# SCH2_Switching.net
KiCad netlist of a schematic drawn in Altium Designer
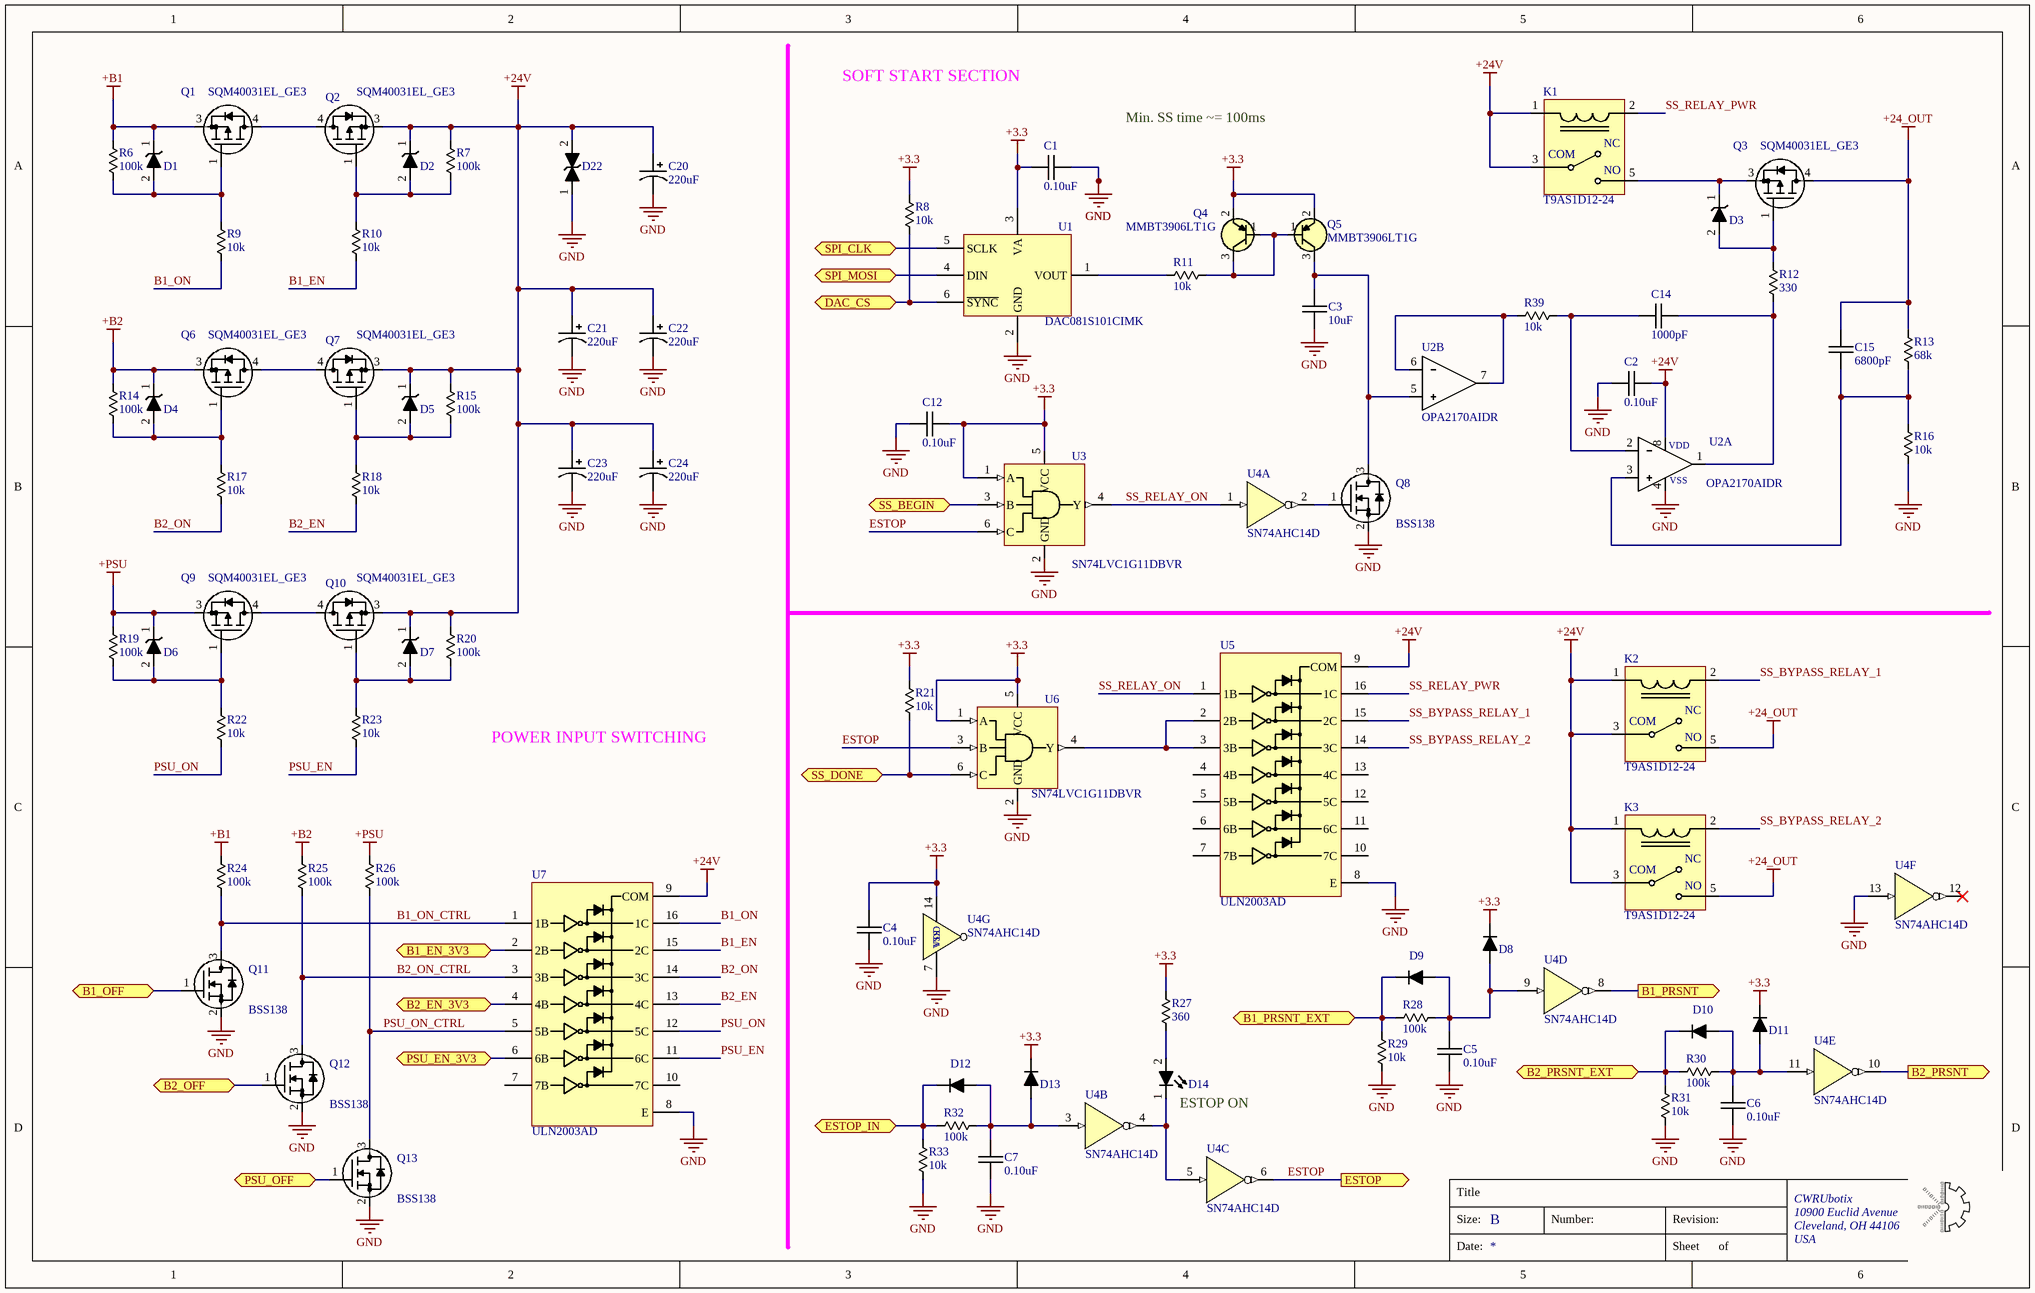
[diagram p0: SCH2_Switching.SchDoc]

(export (version "E")
  (design (tool "Eeschema 10.0.6"))
  (components
    (comp (ref "C1")
      (value "0.10uF")
      (footprint "chip_0805")
      (description "CAP, 0.10uF, 10%, 25V, X7R, 0805")
      (fields (field (name "PART NUMBER") "CAP-00071") (field (name "TOLERANCE") "10%"))
      (libsource (lib "Capacitors$") (part "CAP-00071"))
    )
    (comp (ref "C2")
      (value "0.10uF")
      (footprint "chip_0805")
      (description "CAP, 0.10uF, 10%, 25V, X7R, 0805")
      (fields (field (name "PART NUMBER") "CAP-00071") (field (name "TOLERANCE") "10%"))
      (libsource (lib "Capacitors$") (part "CAP-00071"))
    )
    (comp (ref "C3")
      (value "10uF")
      (footprint "chip_1206")
      (description "CAP, 10uF, ±10%, 25V, X7R, 1206")
      (fields (field (name "PART NUMBER") "CAP-00539") (field (name "TOLERANCE") "±10%"))
      (libsource (lib "Capacitors$") (part "CAP-00539"))
    )
    (comp (ref "C4")
      (value "0.10uF")
      (footprint "chip_0805")
      (description "CAP, 0.10uF, 10%, 25V, X7R, 0805")
      (fields (field (name "PART NUMBER") "CAP-00071") (field (name "TOLERANCE") "10%"))
      (libsource (lib "Capacitors$") (part "CAP-00071"))
    )
    (comp (ref "C5")
      (value "0.10uF")
      (footprint "chip_0805")
      (description "CAP, 0.10uF, 10%, 25V, X7R, 0805")
      (fields (field (name "PART NUMBER") "CAP-00071") (field (name "TOLERANCE") "10%"))
      (libsource (lib "Capacitors$") (part "CAP-00071"))
    )
    (comp (ref "C6")
      (value "0.10uF")
      (footprint "chip_0805")
      (description "CAP, 0.10uF, 10%, 25V, X7R, 0805")
      (fields (field (name "PART NUMBER") "CAP-00071") (field (name "TOLERANCE") "10%"))
      (libsource (lib "Capacitors$") (part "CAP-00071"))
    )
    (comp (ref "C7")
      (value "0.10uF")
      (footprint "chip_0805")
      (description "CAP, 0.10uF, 10%, 25V, X7R, 0805")
      (fields (field (name "PART NUMBER") "CAP-00071") (field (name "TOLERANCE") "10%"))
      (libsource (lib "Capacitors$") (part "CAP-00071"))
    )
    (comp (ref "C12")
      (value "0.10uF")
      (footprint "chip_0805")
      (description "CAP, 0.10uF, 10%, 16V, X7R, 0805")
      (fields (field (name "PART NUMBER") "CAP-00069") (field (name "TOLERANCE") "10%"))
      (libsource (lib "Capacitors$") (part "CAP-00069"))
    )
    (comp (ref "C14")
      (value "1000pF")
      (footprint "chip_0805")
      (description "CAP, 1000pF, 10%, 50V, X7R, 0805")
      (fields (field (name "PART NUMBER") "CAP-00009") (field (name "TOLERANCE") "10%"))
      (libsource (lib "Capacitors$") (part "CAP-00009"))
    )
    (comp (ref "C15")
      (value "6800pF")
      (footprint "chip_0805")
      (description "CAP, 6800pF, 10%, 50V, X7R, 0805")
      (fields (field (name "PART NUMBER") "CAP-00035") (field (name "TOLERANCE") "10%"))
      (libsource (lib "Capacitors$") (part "CAP-00035"))
    )
    (comp (ref "C20")
      (value "220uF")
      (footprint "CP_RADIAL_D10.0_P5.0_H20.0")
      (description "CAP, 220uF, ±20%, 63V, Al, 5000hrs @ 105°C")
      (fields (field (name "PART NUMBER") "CAP-00591") (field (name "TOLERANCE") "±20%"))
      (libsource (lib "Capacitors$") (part "CAP-00591"))
    )
    (comp (ref "C21")
      (value "220uF")
      (footprint "CP_RADIAL_D10.0_P5.0_H20.0")
      (description "CAP, 220uF, ±20%, 63V, Al, 5000hrs @ 105°C")
      (fields (field (name "PART NUMBER") "CAP-00591") (field (name "TOLERANCE") "±20%"))
      (libsource (lib "Capacitors$") (part "CAP-00591"))
    )
    (comp (ref "C22")
      (value "220uF")
      (footprint "CP_RADIAL_D10.0_P5.0_H20.0")
      (description "CAP, 220uF, ±20%, 63V, Al, 5000hrs @ 105°C")
      (fields (field (name "PART NUMBER") "CAP-00591") (field (name "TOLERANCE") "±20%"))
      (libsource (lib "Capacitors$") (part "CAP-00591"))
    )
    (comp (ref "C23")
      (value "220uF")
      (footprint "CP_RADIAL_D10.0_P5.0_H20.0")
      (description "CAP, 220uF, ±20%, 63V, Al, 5000hrs @ 105°C")
      (fields (field (name "PART NUMBER") "CAP-00591") (field (name "TOLERANCE") "±20%"))
      (libsource (lib "Capacitors$") (part "CAP-00591"))
    )
    (comp (ref "C24")
      (value "220uF")
      (footprint "CP_RADIAL_D10.0_P5.0_H20.0")
      (description "CAP, 220uF, ±20%, 63V, Al, 5000hrs @ 105°C")
      (fields (field (name "PART NUMBER") "CAP-00591") (field (name "TOLERANCE") "±20%"))
      (libsource (lib "Capacitors$") (part "CAP-00591"))
    )
    (comp (ref "D1")
      (value "diode_1")
      (footprint "sod123_0")
      (description "Dio, Zener, 12V 5% 500mW SOD-123")
      (fields (field (name "PART NUMBER") "DIO-00072") (field (name "TOLERANCE") "5%"))
      (libsource (lib "Diodes$") (part "DIO-00072"))
    )
    (comp (ref "D2")
      (value "diode_1")
      (footprint "sod123_0")
      (description "Dio, Zener, 12V 5% 500mW SOD-123")
      (fields (field (name "PART NUMBER") "DIO-00072") (field (name "TOLERANCE") "5%"))
      (libsource (lib "Diodes$") (part "DIO-00072"))
    )
    (comp (ref "D3")
      (value "diode_1")
      (footprint "sod123_0")
      (description "Dio, Zener, 12V 5% 500mW SOD-123")
      (fields (field (name "PART NUMBER") "DIO-00072") (field (name "TOLERANCE") "5%"))
      (libsource (lib "Diodes$") (part "DIO-00072"))
    )
    (comp (ref "D4")
      (value "diode_1")
      (footprint "sod123_0")
      (description "Dio, Zener, 12V 5% 500mW SOD-123")
      (fields (field (name "PART NUMBER") "DIO-00072") (field (name "TOLERANCE") "5%"))
      (libsource (lib "Diodes$") (part "DIO-00072"))
    )
    (comp (ref "D5")
      (value "diode_1")
      (footprint "sod123_0")
      (description "Dio, Zener, 12V 5% 500mW SOD-123")
      (fields (field (name "PART NUMBER") "DIO-00072") (field (name "TOLERANCE") "5%"))
      (libsource (lib "Diodes$") (part "DIO-00072"))
    )
    (comp (ref "D6")
      (value "diode_1")
      (footprint "sod123_0")
      (description "Dio, Zener, 12V 5% 500mW SOD-123")
      (fields (field (name "PART NUMBER") "DIO-00072") (field (name "TOLERANCE") "5%"))
      (libsource (lib "Diodes$") (part "DIO-00072"))
    )
    (comp (ref "D7")
      (value "diode_1")
      (footprint "sod123_0")
      (description "Dio, Zener, 12V 5% 500mW SOD-123")
      (fields (field (name "PART NUMBER") "DIO-00072") (field (name "TOLERANCE") "5%"))
      (libsource (lib "Diodes$") (part "DIO-00072"))
    )
    (comp (ref "D8")
      (value "diode_0")
      (footprint "sod123_0")
      (description "Dio, Silicon, 200mA, 1V, 100V, SOD-123")
      (fields (field (name "PART NUMBER") "DIO-00060") (field (name "MANUFACTURER") "ON Semi"))
      (libsource (lib "Diodes$") (part "DIO-00060"))
    )
    (comp (ref "D9")
      (value "diode_0")
      (footprint "sod123_0")
      (description "Dio, Silicon, 200mA, 1V, 100V, SOD-123")
      (fields (field (name "PART NUMBER") "DIO-00060") (field (name "MANUFACTURER") "ON Semi"))
      (libsource (lib "Diodes$") (part "DIO-00060"))
    )
    (comp (ref "D10")
      (value "diode_0")
      (footprint "sod123_0")
      (description "Dio, Silicon, 200mA, 1V, 100V, SOD-123")
      (fields (field (name "PART NUMBER") "DIO-00060") (field (name "MANUFACTURER") "ON Semi"))
      (libsource (lib "Diodes$") (part "DIO-00060"))
    )
    (comp (ref "D11")
      (value "diode_0")
      (footprint "sod123_0")
      (description "Dio, Silicon, 200mA, 1V, 100V, SOD-123")
      (fields (field (name "PART NUMBER") "DIO-00060") (field (name "MANUFACTURER") "ON Semi"))
      (libsource (lib "Diodes$") (part "DIO-00060"))
    )
    (comp (ref "D12")
      (value "diode_0")
      (footprint "sod123_0")
      (description "Dio, Silicon, 200mA, 1V, 100V, SOD-123")
      (fields (field (name "PART NUMBER") "DIO-00060") (field (name "MANUFACTURER") "ON Semi"))
      (libsource (lib "Diodes$") (part "DIO-00060"))
    )
    (comp (ref "D13")
      (value "diode_0")
      (footprint "sod123_0")
      (description "Dio, Silicon, 200mA, 1V, 100V, SOD-123")
      (fields (field (name "PART NUMBER") "DIO-00060") (field (name "MANUFACTURER") "ON Semi"))
      (libsource (lib "Diodes$") (part "DIO-00060"))
    )
    (comp (ref "D14")
      (value "diode_4")
      (footprint "chip_0603_LED")
      (description "LED, Blue, 0603, Low current, HELI2 Series")
      (fields (field (name "PART NUMBER") "DIO-00049") (field (name "MANUFACTURER") "Kingbright"))
      (libsource (lib "Diodes$") (part "DIO-00049"))
    )
    (comp (ref "D22")
      (value "diode_5")
      (footprint "do-214ab")
      (description "TVS, 28V, 45.5V@66A, 3kW 66A Peak, Bidirectional, DO-214AC")
      (fields (field (name "PART NUMBER") "DIO-00090") (field (name "MANUFACTURER") "ST"))
      (libsource (lib "Diodes$") (part "DIO-00090"))
    )
    (comp (ref "K1")
      (value "T9AS1D12-24")
      (footprint "TE_CONN_T9AS")
      (description "Relay, 24V Coil, 30A, SPST, 1 Form A")
      (fields (field (name "PART NUMBER") "MISC-00050") (field (name "MANUFACTURER") "TE Connectivity"))
      (libsource (lib "Misc$") (part "MISC-00050"))
    )
    (comp (ref "K2")
      (value "T9AS1D12-24")
      (footprint "TE_CONN_T9AS")
      (description "Relay, 24V Coil, 30A, SPST, 1 Form A")
      (fields (field (name "PART NUMBER") "MISC-00050") (field (name "MANUFACTURER") "TE Connectivity"))
      (libsource (lib "Misc$") (part "MISC-00050"))
    )
    (comp (ref "K3")
      (value "T9AS1D12-24")
      (footprint "TE_CONN_T9AS")
      (description "Relay, 24V Coil, 30A, SPST, 1 Form A")
      (fields (field (name "PART NUMBER") "MISC-00050") (field (name "MANUFACTURER") "TE Connectivity"))
      (libsource (lib "Misc$") (part "MISC-00050"))
    )
    (comp (ref "Q1")
      (value "SQM40031EL_GE3")
      (footprint "D2PAK-3_1")
      (description "XSTR, MOSFET P-Channel, 40V 120A 3mOhm Rds On, D2PAK")
      (fields (field (name "PART NUMBER") "XSTR-00046") (field (name "MANUFACTURER") "Vishay Siliconix"))
      (libsource (lib "Transistors$") (part "XSTR-00046"))
    )
    (comp (ref "Q2")
      (value "SQM40031EL_GE3")
      (footprint "D2PAK-3_1")
      (description "XSTR, MOSFET P-Channel, 40V 120A 3mOhm Rds On, D2PAK")
      (fields (field (name "PART NUMBER") "XSTR-00046") (field (name "MANUFACTURER") "Vishay Siliconix"))
      (libsource (lib "Transistors$") (part "XSTR-00046"))
    )
    (comp (ref "Q3")
      (value "SQM40031EL_GE3")
      (footprint "D2PAK-3_1")
      (description "XSTR, MOSFET P-Channel, 40V 120A 3mOhm Rds On, D2PAK")
      (fields (field (name "PART NUMBER") "XSTR-00046") (field (name "MANUFACTURER") "Vishay Siliconix"))
      (libsource (lib "Transistors$") (part "XSTR-00046"))
    )
    (comp (ref "Q4")
      (value "MMBT3906LT1G")
      (footprint "SOT-23-3_1")
      (description "XSTR, PNP, 200mA, 40V, Vce 0.4V, SOT-23-3")
      (fields (field (name "PART NUMBER") "XSTR-00038") (field (name "MANUFACTURER") "ON Semi"))
      (libsource (lib "Transistors$") (part "XSTR-00038"))
    )
    (comp (ref "Q5")
      (value "MMBT3906LT1G")
      (footprint "SOT-23-3_1")
      (description "XSTR, PNP, 200mA, 40V, Vce 0.4V, SOT-23-3")
      (fields (field (name "PART NUMBER") "XSTR-00038") (field (name "MANUFACTURER") "ON Semi"))
      (libsource (lib "Transistors$") (part "XSTR-00038"))
    )
    (comp (ref "Q6")
      (value "SQM40031EL_GE3")
      (footprint "D2PAK-3_1")
      (description "XSTR, MOSFET P-Channel, 40V 120A 3mOhm Rds On, D2PAK")
      (fields (field (name "PART NUMBER") "XSTR-00046") (field (name "MANUFACTURER") "Vishay Siliconix"))
      (libsource (lib "Transistors$") (part "XSTR-00046"))
    )
    (comp (ref "Q7")
      (value "SQM40031EL_GE3")
      (footprint "D2PAK-3_1")
      (description "XSTR, MOSFET P-Channel, 40V 120A 3mOhm Rds On, D2PAK")
      (fields (field (name "PART NUMBER") "XSTR-00046") (field (name "MANUFACTURER") "Vishay Siliconix"))
      (libsource (lib "Transistors$") (part "XSTR-00046"))
    )
    (comp (ref "Q8")
      (value "BSS138")
      (footprint "sot-23-3")
      (description "XSTR NMOS, 220mA, 50V, Vgs 1.3V, SOT-23-3")
      (fields (field (name "PART NUMBER") "XSTR-00017") (field (name "MANUFACTURER") "ON Semi"))
      (libsource (lib "Transistors$") (part "XSTR-00017"))
    )
    (comp (ref "Q9")
      (value "SQM40031EL_GE3")
      (footprint "D2PAK-3_1")
      (description "XSTR, MOSFET P-Channel, 40V 120A 3mOhm Rds On, D2PAK")
      (fields (field (name "PART NUMBER") "XSTR-00046") (field (name "MANUFACTURER") "Vishay Siliconix"))
      (libsource (lib "Transistors$") (part "XSTR-00046"))
    )
    (comp (ref "Q10")
      (value "SQM40031EL_GE3")
      (footprint "D2PAK-3_1")
      (description "XSTR, MOSFET P-Channel, 40V 120A 3mOhm Rds On, D2PAK")
      (fields (field (name "PART NUMBER") "XSTR-00046") (field (name "MANUFACTURER") "Vishay Siliconix"))
      (libsource (lib "Transistors$") (part "XSTR-00046"))
    )
    (comp (ref "Q11")
      (value "BSS138")
      (footprint "sot-23-3")
      (description "XSTR NMOS, 220mA, 50V, Vgs 1.3V, SOT-23-3")
      (fields (field (name "PART NUMBER") "XSTR-00017") (field (name "MANUFACTURER") "ON Semi"))
      (libsource (lib "Transistors$") (part "XSTR-00017"))
    )
    (comp (ref "Q12")
      (value "BSS138")
      (footprint "sot-23-3")
      (description "XSTR NMOS, 220mA, 50V, Vgs 1.3V, SOT-23-3")
      (fields (field (name "PART NUMBER") "XSTR-00017") (field (name "MANUFACTURER") "ON Semi"))
      (libsource (lib "Transistors$") (part "XSTR-00017"))
    )
    (comp (ref "Q13")
      (value "BSS138")
      (footprint "sot-23-3")
      (description "XSTR NMOS, 220mA, 50V, Vgs 1.3V, SOT-23-3")
      (fields (field (name "PART NUMBER") "XSTR-00017") (field (name "MANUFACTURER") "ON Semi"))
      (libsource (lib "Transistors$") (part "XSTR-00017"))
    )
    (comp (ref "R6")
      (value "100k")
      (footprint "chip_0805")
      (description "RES SMD 100K OHM 1% 1/8W 0805")
      (fields (field (name "PART NUMBER") "RES-00302") (field (name "TOLERANCE") "1%"))
      (libsource (lib "Resistors$") (part "RES-00302"))
    )
    (comp (ref "R7")
      (value "100k")
      (footprint "chip_0805")
      (description "RES SMD 100K OHM 1% 1/8W 0805")
      (fields (field (name "PART NUMBER") "RES-00302") (field (name "TOLERANCE") "1%"))
      (libsource (lib "Resistors$") (part "RES-00302"))
    )
    (comp (ref "R8")
      (value "10k")
      (footprint "chip_0805")
      (description "RES SMD 10K OHM 1% 1/8W 0805")
      (fields (field (name "PART NUMBER") "RES-00307") (field (name "TOLERANCE") "1%"))
      (libsource (lib "Resistors$") (part "RES-00307"))
    )
    (comp (ref "R9")
      (value "10k")
      (footprint "chip_0805")
      (description "RES SMD 10K OHM 1% 1/8W 0805")
      (fields (field (name "PART NUMBER") "RES-00307") (field (name "TOLERANCE") "1%"))
      (libsource (lib "Resistors$") (part "RES-00307"))
    )
    (comp (ref "R10")
      (value "10k")
      (footprint "chip_0805")
      (description "RES SMD 10K OHM 1% 1/8W 0805")
      (fields (field (name "PART NUMBER") "RES-00307") (field (name "TOLERANCE") "1%"))
      (libsource (lib "Resistors$") (part "RES-00307"))
    )
    (comp (ref "R11")
      (value "10k")
      (footprint "chip_0805")
      (description "RES SMD 10K OHM 1% 1/8W 0805")
      (fields (field (name "PART NUMBER") "RES-00307") (field (name "TOLERANCE") "1%"))
      (libsource (lib "Resistors$") (part "RES-00307"))
    )
    (comp (ref "R12")
      (value "330")
      (footprint "chip_0805")
      (description "RES SMD 330 OHM 1% 1/8W 0805")
      (fields (field (name "PART NUMBER") "RES-00222") (field (name "TOLERANCE") "1%"))
      (libsource (lib "Resistors$") (part "RES-00222"))
    )
    (comp (ref "R13")
      (value "68k")
      (footprint "chip_0805")
      (description "RES SMD 68K OHM 1% 1/8W 0805 100ppm")
      (fields (field (name "PART NUMBER") "RES-00724") (field (name "TOLERANCE") "1%"))
      (libsource (lib "Resistors$") (part "RES-00724"))
    )
    (comp (ref "R14")
      (value "100k")
      (footprint "chip_0805")
      (description "RES SMD 100K OHM 1% 1/8W 0805")
      (fields (field (name "PART NUMBER") "RES-00302") (field (name "TOLERANCE") "1%"))
      (libsource (lib "Resistors$") (part "RES-00302"))
    )
    (comp (ref "R15")
      (value "100k")
      (footprint "chip_0805")
      (description "RES SMD 100K OHM 1% 1/8W 0805")
      (fields (field (name "PART NUMBER") "RES-00302") (field (name "TOLERANCE") "1%"))
      (libsource (lib "Resistors$") (part "RES-00302"))
    )
    (comp (ref "R16")
      (value "10k")
      (footprint "chip_0805")
      (description "RES SMD 10K OHM 1% 1/8W 0805")
      (fields (field (name "PART NUMBER") "RES-00307") (field (name "TOLERANCE") "1%"))
      (libsource (lib "Resistors$") (part "RES-00307"))
    )
    (comp (ref "R17")
      (value "10k")
      (footprint "chip_0805")
      (description "RES SMD 10K OHM 1% 1/8W 0805")
      (fields (field (name "PART NUMBER") "RES-00307") (field (name "TOLERANCE") "1%"))
      (libsource (lib "Resistors$") (part "RES-00307"))
    )
    (comp (ref "R18")
      (value "10k")
      (footprint "chip_0805")
      (description "RES SMD 10K OHM 1% 1/8W 0805")
      (fields (field (name "PART NUMBER") "RES-00307") (field (name "TOLERANCE") "1%"))
      (libsource (lib "Resistors$") (part "RES-00307"))
    )
    (comp (ref "R19")
      (value "100k")
      (footprint "chip_0805")
      (description "RES SMD 100K OHM 1% 1/8W 0805")
      (fields (field (name "PART NUMBER") "RES-00302") (field (name "TOLERANCE") "1%"))
      (libsource (lib "Resistors$") (part "RES-00302"))
    )
    (comp (ref "R20")
      (value "100k")
      (footprint "chip_0805")
      (description "RES SMD 100K OHM 1% 1/8W 0805")
      (fields (field (name "PART NUMBER") "RES-00302") (field (name "TOLERANCE") "1%"))
      (libsource (lib "Resistors$") (part "RES-00302"))
    )
    (comp (ref "R21")
      (value "10k")
      (footprint "chip_0805")
      (description "RES SMD 10K OHM 1% 1/8W 0805")
      (fields (field (name "PART NUMBER") "RES-00307") (field (name "TOLERANCE") "1%"))
      (libsource (lib "Resistors$") (part "RES-00307"))
    )
    (comp (ref "R22")
      (value "10k")
      (footprint "chip_0805")
      (description "RES SMD 10K OHM 1% 1/8W 0805")
      (fields (field (name "PART NUMBER") "RES-00307") (field (name "TOLERANCE") "1%"))
      (libsource (lib "Resistors$") (part "RES-00307"))
    )
    (comp (ref "R23")
      (value "10k")
      (footprint "chip_0805")
      (description "RES SMD 10K OHM 1% 1/8W 0805")
      (fields (field (name "PART NUMBER") "RES-00307") (field (name "TOLERANCE") "1%"))
      (libsource (lib "Resistors$") (part "RES-00307"))
    )
    (comp (ref "R24")
      (value "100k")
      (footprint "chip_0805")
      (description "RES SMD 100K OHM 1% 1/8W 0805")
      (fields (field (name "PART NUMBER") "RES-00302") (field (name "TOLERANCE") "1%"))
      (libsource (lib "Resistors$") (part "RES-00302"))
    )
    (comp (ref "R25")
      (value "100k")
      (footprint "chip_0805")
      (description "RES SMD 100K OHM 1% 1/8W 0805")
      (fields (field (name "PART NUMBER") "RES-00302") (field (name "TOLERANCE") "1%"))
      (libsource (lib "Resistors$") (part "RES-00302"))
    )
    (comp (ref "R26")
      (value "100k")
      (footprint "chip_0805")
      (description "RES SMD 100K OHM 1% 1/8W 0805")
      (fields (field (name "PART NUMBER") "RES-00302") (field (name "TOLERANCE") "1%"))
      (libsource (lib "Resistors$") (part "RES-00302"))
    )
    (comp (ref "R27")
      (value "360")
      (footprint "chip_0805")
      (description "RES SMD 360 OHM 1% 1/8W 0805")
      (fields (field (name "PART NUMBER") "RES-00226") (field (name "TOLERANCE") "1%"))
      (libsource (lib "Resistors$") (part "RES-00226"))
    )
    (comp (ref "R28")
      (value "100k")
      (footprint "chip_0805")
      (description "RES SMD 100K OHM 1% 1/8W 0805")
      (fields (field (name "PART NUMBER") "RES-00302") (field (name "TOLERANCE") "1%"))
      (libsource (lib "Resistors$") (part "RES-00302"))
    )
    (comp (ref "R29")
      (value "10k")
      (footprint "chip_0805")
      (description "RES SMD 10K OHM 1% 1/8W 0805")
      (fields (field (name "PART NUMBER") "RES-00307") (field (name "TOLERANCE") "1%"))
      (libsource (lib "Resistors$") (part "RES-00307"))
    )
    (comp (ref "R30")
      (value "100k")
      (footprint "chip_0805")
      (description "RES SMD 100K OHM 1% 1/8W 0805")
      (fields (field (name "PART NUMBER") "RES-00302") (field (name "TOLERANCE") "1%"))
      (libsource (lib "Resistors$") (part "RES-00302"))
    )
    (comp (ref "R31")
      (value "10k")
      (footprint "chip_0805")
      (description "RES SMD 10K OHM 1% 1/8W 0805")
      (fields (field (name "PART NUMBER") "RES-00307") (field (name "TOLERANCE") "1%"))
      (libsource (lib "Resistors$") (part "RES-00307"))
    )
    (comp (ref "R32")
      (value "100k")
      (footprint "chip_0805")
      (description "RES SMD 100K OHM 1% 1/8W 0805")
      (fields (field (name "PART NUMBER") "RES-00302") (field (name "TOLERANCE") "1%"))
      (libsource (lib "Resistors$") (part "RES-00302"))
    )
    (comp (ref "R33")
      (value "10k")
      (footprint "chip_0805")
      (description "RES SMD 10K OHM 1% 1/8W 0805")
      (fields (field (name "PART NUMBER") "RES-00307") (field (name "TOLERANCE") "1%"))
      (libsource (lib "Resistors$") (part "RES-00307"))
    )
    (comp (ref "R39")
      (value "10k")
      (footprint "chip_0805")
      (description "RES SMD 10K OHM 1% 1/8W 0805")
      (fields (field (name "PART NUMBER") "RES-00307") (field (name "TOLERANCE") "1%"))
      (libsource (lib "Resistors$") (part "RES-00307"))
    )
    (comp (ref "U1")
      (value "DAC081S101CIMK")
      (footprint "TSOT-23-6")
      (description "IC, DAC, 8-bit, Rail-Rail Output, SPI, 2.7~5.5V")
      (fields (field (name "PART NUMBER") "ANLG-00080") (field (name "MANUFACTURER") "TI"))
      (libsource (lib "Analog$") (part "ANLG-00080"))
    )
    (comp (ref "U2")
      (value "OPA2170AIDR")
      (footprint "SO-8_1")
      (description "Op Amp, Dual, Rail-Rail, 2.7~36V, 2.1-MHz, SOIC-8")
      (fields (field (name "PART NUMBER") "ANLG-00068") (field (name "MANUFACTURER") "TI"))
      (libsource (lib "Analog$") (part "ANLG-00068"))
    )
    (comp (ref "U3")
      (value "SN74LVC1G11DBVR")
      (footprint "sot-23-6")
      (description "IC, AND Gate, Single 3-Input, 1.65-5.5V, SOT-23-6")
      (fields (field (name "PART NUMBER") "LOGIC-00042") (field (name "MANUFACTURER") "TI"))
      (libsource (lib "Logic$") (part "LOGIC-00042"))
    )
    (comp (ref "U4")
      (value "SN74AHC14D")
      (footprint "SO-14")
      (description "IC, Inverter, Hex, Schmitt Triggered Inputs, SOIC-14, SN74ACH14D")
      (fields (field (name "PART NUMBER") "LOGIC-00014") (field (name "MANUFACTURER") "TI"))
      (libsource (lib "Logic$") (part "LOGIC-00014"))
    )
    (comp (ref "U5")
      (value "ULN2003AD")
      (footprint "SO-16_1")
      (description "IC, 7 NPN Darlington Array, 50V 500mA")
      (fields (field (name "PART NUMBER") "ANLG-00079") (field (name "MANUFACTURER") "TI"))
      (libsource (lib "Analog$") (part "ANLG-00079"))
    )
    (comp (ref "U6")
      (value "SN74LVC1G11DBVR")
      (footprint "sot-23-6")
      (description "IC, AND Gate, Single 3-Input, 1.65-5.5V, SOT-23-6")
      (fields (field (name "PART NUMBER") "LOGIC-00042") (field (name "MANUFACTURER") "TI"))
      (libsource (lib "Logic$") (part "LOGIC-00042"))
    )
    (comp (ref "U7")
      (value "ULN2003AD")
      (footprint "SO-16_1")
      (description "IC, 7 NPN Darlington Array, 50V 500mA")
      (fields (field (name "PART NUMBER") "ANLG-00079") (field (name "MANUFACTURER") "TI"))
      (libsource (lib "Analog$") (part "ANLG-00079"))
    )
  )
  (nets
    (net (code "1") (name "+3.3") (class "Default")
      (node (ref "C1") (pin "2") (pinfunction "2_2") (pintype "passive"))
      (node (ref "C12") (pin "2") (pinfunction "2_2") (pintype "passive"))
      (node (ref "C4") (pin "2") (pinfunction "2_2") (pintype "passive"))
      (node (ref "D11") (pin "1") (pinfunction "1_1") (pintype "passive"))
      (node (ref "D13") (pin "1") (pinfunction "1_1") (pintype "passive"))
      (node (ref "D8") (pin "1") (pinfunction "1_1") (pintype "passive"))
      (node (ref "Q4") (pin "2") (pinfunction "E_2") (pintype "passive"))
      (node (ref "Q5") (pin "2") (pinfunction "E_2") (pintype "passive"))
      (node (ref "R21") (pin "2") (pinfunction "2_2") (pintype "passive"))
      (node (ref "R27") (pin "1") (pinfunction "1_1") (pintype "passive"))
      (node (ref "R8") (pin "2") (pinfunction "2_2") (pintype "passive"))
      (node (ref "U1") (pin "3") (pinfunction "VA_3") (pintype "passive"))
      (node (ref "U3") (pin "1") (pinfunction "A_1") (pintype "input"))
      (node (ref "U3") (pin "5") (pinfunction "VCC_5") (pintype "power_in"))
      (node (ref "U4") (pin "14") (pinfunction "VDD_14") (pintype "power_in"))
      (node (ref "U6") (pin "1") (pinfunction "A_1") (pintype "input"))
      (node (ref "U6") (pin "5") (pinfunction "VCC_5") (pintype "power_in"))
    )
    (net (code "2") (name "+24V") (class "Default")
      (node (ref "C2") (pin "2") (pinfunction "2_2") (pintype "passive"))
      (node (ref "C20") (pin "1") (pinfunction "1_1") (pintype "passive"))
      (node (ref "C21") (pin "1") (pinfunction "1_1") (pintype "passive"))
      (node (ref "C22") (pin "1") (pinfunction "1_1") (pintype "passive"))
      (node (ref "C23") (pin "1") (pinfunction "1_1") (pintype "passive"))
      (node (ref "C24") (pin "1") (pinfunction "1_1") (pintype "passive"))
      (node (ref "D2") (pin "1") (pinfunction "1_1") (pintype "passive"))
      (node (ref "D22") (pin "2") (pinfunction "2_2") (pintype "passive"))
      (node (ref "D5") (pin "1") (pinfunction "1_1") (pintype "passive"))
      (node (ref "D7") (pin "1") (pinfunction "1_1") (pintype "passive"))
      (node (ref "K1") (pin "1") (pinfunction "1_1") (pintype "passive"))
      (node (ref "K1") (pin "3") (pinfunction "COM_3") (pintype "passive"))
      (node (ref "K2") (pin "1") (pinfunction "1_1") (pintype "passive"))
      (node (ref "K2") (pin "3") (pinfunction "COM_3") (pintype "passive"))
      (node (ref "K3") (pin "1") (pinfunction "1_1") (pintype "passive"))
      (node (ref "K3") (pin "3") (pinfunction "COM_3") (pintype "passive"))
      (node (ref "Q10") (pin "3") (pinfunction "S_3") (pintype "passive"))
      (node (ref "Q2") (pin "3") (pinfunction "S_3") (pintype "passive"))
      (node (ref "Q7") (pin "3") (pinfunction "S_3") (pintype "passive"))
      (node (ref "R15") (pin "1") (pinfunction "1_1") (pintype "passive"))
      (node (ref "R20") (pin "1") (pinfunction "1_1") (pintype "passive"))
      (node (ref "R7") (pin "1") (pinfunction "1_1") (pintype "passive"))
      (node (ref "U2") (pin "8") (pinfunction "8_8") (pintype "passive"))
      (node (ref "U5") (pin "9") (pinfunction "COM_9") (pintype "passive"))
      (node (ref "U7") (pin "9") (pinfunction "COM_9") (pintype "passive"))
    )
    (net (code "3") (name "+24_OUT") (class "Default")
      (node (ref "C15") (pin "1") (pinfunction "1_1") (pintype "passive"))
      (node (ref "K2") (pin "5") (pinfunction "NO_5") (pintype "passive"))
      (node (ref "K3") (pin "5") (pinfunction "NO_5") (pintype "passive"))
      (node (ref "Q3") (pin "4") (pinfunction "D_4") (pintype "passive"))
      (node (ref "R13") (pin "1") (pinfunction "1_1") (pintype "passive"))
    )
    (net (code "4") (name "+B1") (class "Default")
      (node (ref "D1") (pin "1") (pinfunction "1_1") (pintype "passive"))
      (node (ref "Q1") (pin "3") (pinfunction "S_3") (pintype "passive"))
      (node (ref "R24") (pin "1") (pinfunction "1_1") (pintype "passive"))
      (node (ref "R6") (pin "1") (pinfunction "1_1") (pintype "passive"))
    )
    (net (code "5") (name "+B2") (class "Default")
      (node (ref "D4") (pin "1") (pinfunction "1_1") (pintype "passive"))
      (node (ref "Q6") (pin "3") (pinfunction "S_3") (pintype "passive"))
      (node (ref "R14") (pin "1") (pinfunction "1_1") (pintype "passive"))
      (node (ref "R25") (pin "1") (pinfunction "1_1") (pintype "passive"))
    )
    (net (code "6") (name "+PSU") (class "Default")
      (node (ref "D6") (pin "1") (pinfunction "1_1") (pintype "passive"))
      (node (ref "Q9") (pin "3") (pinfunction "S_3") (pintype "passive"))
      (node (ref "R19") (pin "1") (pinfunction "1_1") (pintype "passive"))
      (node (ref "R26") (pin "1") (pinfunction "1_1") (pintype "passive"))
    )
    (net (code "7") (name "/B1_EN") (class "Default")
      (node (ref "R10") (pin "2") (pinfunction "2_2") (pintype "passive"))
      (node (ref "U7") (pin "15") (pinfunction "2C_15") (pintype "passive"))
    )
    (net (code "8") (name "/B1_EN_3V3") (class "Default")
      (node (ref "U7") (pin "2") (pinfunction "2B_2") (pintype "passive"))
    )
    (net (code "9") (name "/B1_OFF") (class "Default")
      (node (ref "Q11") (pin "1") (pinfunction "G_1") (pintype "passive"))
    )
    (net (code "10") (name "/B1_ON") (class "Default")
      (node (ref "R9") (pin "2") (pinfunction "2_2") (pintype "passive"))
      (node (ref "U7") (pin "16") (pinfunction "1C_16") (pintype "passive"))
    )
    (net (code "11") (name "/B1_ON_CTRL") (class "Default")
      (node (ref "Q11") (pin "3") (pinfunction "D_3") (pintype "passive"))
      (node (ref "R24") (pin "2") (pinfunction "2_2") (pintype "passive"))
      (node (ref "U7") (pin "1") (pinfunction "1B_1") (pintype "passive"))
    )
    (net (code "12") (name "/B1_PRSNT") (class "Default")
      (node (ref "U4") (pin "8") (pinfunction "J_8") (pintype "output"))
    )
    (net (code "13") (name "/B1_PRSNT_EXT") (class "Default")
      (node (ref "D9") (pin "1") (pinfunction "1_1") (pintype "passive"))
      (node (ref "R28") (pin "1") (pinfunction "1_1") (pintype "passive"))
      (node (ref "R29") (pin "2") (pinfunction "2_2") (pintype "passive"))
    )
    (net (code "14") (name "/B2_EN") (class "Default")
      (node (ref "R18") (pin "2") (pinfunction "2_2") (pintype "passive"))
      (node (ref "U7") (pin "13") (pinfunction "4C_13") (pintype "passive"))
    )
    (net (code "15") (name "/B2_EN_3V3") (class "Default")
      (node (ref "U7") (pin "4") (pinfunction "4B_4") (pintype "passive"))
    )
    (net (code "16") (name "/B2_OFF") (class "Default")
      (node (ref "Q12") (pin "1") (pinfunction "G_1") (pintype "passive"))
    )
    (net (code "17") (name "/B2_ON") (class "Default")
      (node (ref "R17") (pin "2") (pinfunction "2_2") (pintype "passive"))
      (node (ref "U7") (pin "14") (pinfunction "3C_14") (pintype "passive"))
    )
    (net (code "18") (name "/B2_ON_CTRL") (class "Default")
      (node (ref "Q12") (pin "3") (pinfunction "D_3") (pintype "passive"))
      (node (ref "R25") (pin "2") (pinfunction "2_2") (pintype "passive"))
      (node (ref "U7") (pin "3") (pinfunction "3B_3") (pintype "passive"))
    )
    (net (code "19") (name "/B2_PRSNT") (class "Default")
      (node (ref "U4") (pin "10") (pinfunction "K_10") (pintype "output"))
    )
    (net (code "20") (name "/B2_PRSNT_EXT") (class "Default")
      (node (ref "D10") (pin "1") (pinfunction "1_1") (pintype "passive"))
      (node (ref "R30") (pin "1") (pinfunction "1_1") (pintype "passive"))
      (node (ref "R31") (pin "2") (pinfunction "2_2") (pintype "passive"))
    )
    (net (code "21") (name "/DAC_CS") (class "Default")
      (node (ref "R8") (pin "1") (pinfunction "1_1") (pintype "passive"))
      (node (ref "U1") (pin "6") (pinfunction "~{SYNC}_6") (pintype "passive"))
    )
    (net (code "22") (name "/ESTOP") (class "Default")
      (node (ref "U3") (pin "6") (pinfunction "C_6") (pintype "input"))
      (node (ref "U4") (pin "6") (pinfunction "~{C}_6") (pintype "output"))
      (node (ref "U6") (pin "3") (pinfunction "B_3") (pintype "input"))
    )
    (net (code "23") (name "/ESTOP_IN") (class "Default")
      (node (ref "D12") (pin "1") (pinfunction "1_1") (pintype "passive"))
      (node (ref "R32") (pin "1") (pinfunction "1_1") (pintype "passive"))
      (node (ref "R33") (pin "2") (pinfunction "2_2") (pintype "passive"))
    )
    (net (code "24") (name "/PSU_EN") (class "Default")
      (node (ref "R23") (pin "2") (pinfunction "2_2") (pintype "passive"))
      (node (ref "U7") (pin "11") (pinfunction "6C_11") (pintype "passive"))
    )
    (net (code "25") (name "/PSU_EN_3V3") (class "Default")
      (node (ref "U7") (pin "6") (pinfunction "6B_6") (pintype "passive"))
    )
    (net (code "26") (name "/PSU_OFF") (class "Default")
      (node (ref "Q13") (pin "1") (pinfunction "G_1") (pintype "passive"))
    )
    (net (code "27") (name "/PSU_ON") (class "Default")
      (node (ref "R22") (pin "2") (pinfunction "2_2") (pintype "passive"))
      (node (ref "U7") (pin "12") (pinfunction "5C_12") (pintype "passive"))
    )
    (net (code "28") (name "/PSU_ON_CTRL") (class "Default")
      (node (ref "Q13") (pin "3") (pinfunction "D_3") (pintype "passive"))
      (node (ref "R26") (pin "2") (pinfunction "2_2") (pintype "passive"))
      (node (ref "U7") (pin "5") (pinfunction "5B_5") (pintype "passive"))
    )
    (net (code "29") (name "/SPI_CLK") (class "Default")
      (node (ref "U1") (pin "5") (pinfunction "SCLK_5") (pintype "passive"))
    )
    (net (code "30") (name "/SPI_MOSI") (class "Default")
      (node (ref "U1") (pin "4") (pinfunction "DIN_4") (pintype "passive"))
    )
    (net (code "31") (name "/SS_BEGIN") (class "Default")
      (node (ref "U3") (pin "3") (pinfunction "B_3") (pintype "input"))
    )
    (net (code "32") (name "/SS_BYPASS_RELAY_1") (class "Default")
      (node (ref "K2") (pin "2") (pinfunction "2_2") (pintype "passive"))
      (node (ref "U5") (pin "15") (pinfunction "2C_15") (pintype "passive"))
    )
    (net (code "33") (name "/SS_BYPASS_RELAY_2") (class "Default")
      (node (ref "K3") (pin "2") (pinfunction "2_2") (pintype "passive"))
      (node (ref "U5") (pin "14") (pinfunction "3C_14") (pintype "passive"))
    )
    (net (code "34") (name "/SS_DONE") (class "Default")
      (node (ref "R21") (pin "1") (pinfunction "1_1") (pintype "passive"))
      (node (ref "U6") (pin "6") (pinfunction "C_6") (pintype "input"))
    )
    (net (code "35") (name "/SS_RELAY_ON") (class "Default")
      (node (ref "U3") (pin "4") (pinfunction "Y_4") (pintype "output"))
      (node (ref "U4") (pin "1") (pinfunction "A_1") (pintype "input"))
      (node (ref "U5") (pin "1") (pinfunction "1B_1") (pintype "passive"))
    )
    (net (code "36") (name "/SS_RELAY_PWR") (class "Default")
      (node (ref "K1") (pin "2") (pinfunction "2_2") (pintype "passive"))
      (node (ref "U5") (pin "16") (pinfunction "1C_16") (pintype "passive"))
    )
    (net (code "37") (name "GND") (class "Default")
      (node (ref "C1") (pin "1") (pinfunction "1_1") (pintype "passive"))
      (node (ref "C12") (pin "1") (pinfunction "1_1") (pintype "passive"))
      (node (ref "C2") (pin "1") (pinfunction "1_1") (pintype "passive"))
      (node (ref "C20") (pin "2") (pinfunction "2_2") (pintype "passive"))
      (node (ref "C21") (pin "2") (pinfunction "2_2") (pintype "passive"))
      (node (ref "C22") (pin "2") (pinfunction "2_2") (pintype "passive"))
      (node (ref "C23") (pin "2") (pinfunction "2_2") (pintype "passive"))
      (node (ref "C24") (pin "2") (pinfunction "2_2") (pintype "passive"))
      (node (ref "C3") (pin "2") (pinfunction "2_2") (pintype "passive"))
      (node (ref "C4") (pin "1") (pinfunction "1_1") (pintype "passive"))
      (node (ref "C5") (pin "1") (pinfunction "1_1") (pintype "passive"))
      (node (ref "C6") (pin "1") (pinfunction "1_1") (pintype "passive"))
      (node (ref "C7") (pin "1") (pinfunction "1_1") (pintype "passive"))
      (node (ref "D22") (pin "1") (pinfunction "1_1") (pintype "passive"))
      (node (ref "Q11") (pin "2") (pinfunction "S_2") (pintype "passive"))
      (node (ref "Q12") (pin "2") (pinfunction "S_2") (pintype "passive"))
      (node (ref "Q13") (pin "2") (pinfunction "S_2") (pintype "passive"))
      (node (ref "Q8") (pin "2") (pinfunction "S_2") (pintype "passive"))
      (node (ref "R16") (pin "2") (pinfunction "2_2") (pintype "passive"))
      (node (ref "R29") (pin "1") (pinfunction "1_1") (pintype "passive"))
      (node (ref "R31") (pin "1") (pinfunction "1_1") (pintype "passive"))
      (node (ref "R33") (pin "1") (pinfunction "1_1") (pintype "passive"))
      (node (ref "U1") (pin "2") (pinfunction "GND_2") (pintype "passive"))
      (node (ref "U2") (pin "4") (pinfunction "4_4") (pintype "passive"))
      (node (ref "U3") (pin "2") (pinfunction "GND_2") (pintype "power_in"))
      (node (ref "U4") (pin "13") (pinfunction "F_13") (pintype "input"))
      (node (ref "U4") (pin "7") (pinfunction "VSS_7") (pintype "power_in"))
      (node (ref "U5") (pin "8") (pinfunction "E_8") (pintype "passive"))
      (node (ref "U6") (pin "2") (pinfunction "GND_2") (pintype "power_in"))
      (node (ref "U7") (pin "8") (pinfunction "E_8") (pintype "passive"))
    )
    (net (code "38") (name "Net-(C14-Pad1)") (class "Default")
      (node (ref "C14") (pin "1") (pinfunction "1_1") (pintype "passive"))
      (node (ref "R39") (pin "2") (pinfunction "2_2") (pintype "passive"))
      (node (ref "U2") (pin "2") (pinfunction "2_2") (pintype "passive"))
    )
    (net (code "39") (name "Net-(C14-Pad2)") (class "Default")
      (node (ref "C14") (pin "2") (pinfunction "2_2") (pintype "passive"))
      (node (ref "R12") (pin "1") (pinfunction "1_1") (pintype "passive"))
      (node (ref "U2") (pin "1") (pinfunction "1_1") (pintype "passive"))
    )
    (net (code "40") (name "Net-(C15-Pad2)") (class "Default")
      (node (ref "C15") (pin "2") (pinfunction "2_2") (pintype "passive"))
      (node (ref "R13") (pin "2") (pinfunction "2_2") (pintype "passive"))
      (node (ref "R16") (pin "1") (pinfunction "1_1") (pintype "passive"))
      (node (ref "U2") (pin "3") (pinfunction "3_3") (pintype "passive"))
    )
    (net (code "41") (name "Net-(D14-Pad2)") (class "Default")
      (node (ref "D14") (pin "2") (pinfunction "2_2") (pintype "passive"))
      (node (ref "R27") (pin "2") (pinfunction "2_2") (pintype "passive"))
    )
    (net (code "42") (name "Net-(K1-NO)") (class "Default")
      (node (ref "D3") (pin "1") (pinfunction "1_1") (pintype "passive"))
      (node (ref "K1") (pin "5") (pinfunction "NO_5") (pintype "passive"))
      (node (ref "Q3") (pin "3") (pinfunction "S_3") (pintype "passive"))
    )
    (net (code "43") (name "Net-(Q1-D)") (class "Default")
      (node (ref "Q1") (pin "4") (pinfunction "D_4") (pintype "passive"))
      (node (ref "Q2") (pin "4") (pinfunction "D_4") (pintype "passive"))
    )
    (net (code "44") (name "Net-(Q1-G)") (class "Default")
      (node (ref "D1") (pin "2") (pinfunction "2_2") (pintype "passive"))
      (node (ref "Q1") (pin "1") (pinfunction "G_1") (pintype "passive"))
      (node (ref "R6") (pin "2") (pinfunction "2_2") (pintype "passive"))
      (node (ref "R9") (pin "1") (pinfunction "1_1") (pintype "passive"))
    )
    (net (code "45") (name "Net-(Q2-G)") (class "Default")
      (node (ref "D2") (pin "2") (pinfunction "2_2") (pintype "passive"))
      (node (ref "Q2") (pin "1") (pinfunction "G_1") (pintype "passive"))
      (node (ref "R10") (pin "1") (pinfunction "1_1") (pintype "passive"))
      (node (ref "R7") (pin "2") (pinfunction "2_2") (pintype "passive"))
    )
    (net (code "46") (name "Net-(Q3-G)") (class "Default")
      (node (ref "D3") (pin "2") (pinfunction "2_2") (pintype "passive"))
      (node (ref "Q3") (pin "1") (pinfunction "G_1") (pintype "passive"))
      (node (ref "R12") (pin "2") (pinfunction "2_2") (pintype "passive"))
    )
    (net (code "47") (name "Net-(Q4-B)") (class "Default")
      (node (ref "Q4") (pin "1") (pinfunction "B_1") (pintype "passive"))
      (node (ref "Q4") (pin "3") (pinfunction "C_3") (pintype "passive"))
      (node (ref "Q5") (pin "1") (pinfunction "B_1") (pintype "passive"))
      (node (ref "R11") (pin "2") (pinfunction "2_2") (pintype "passive"))
    )
    (net (code "48") (name "Net-(Q5-C)") (class "Default")
      (node (ref "C3") (pin "1") (pinfunction "1_1") (pintype "passive"))
      (node (ref "Q5") (pin "3") (pinfunction "C_3") (pintype "passive"))
      (node (ref "Q8") (pin "3") (pinfunction "D_3") (pintype "passive"))
      (node (ref "U2") (pin "5") (pinfunction "5_5") (pintype "passive"))
    )
    (net (code "49") (name "Net-(Q6-D)") (class "Default")
      (node (ref "Q6") (pin "4") (pinfunction "D_4") (pintype "passive"))
      (node (ref "Q7") (pin "4") (pinfunction "D_4") (pintype "passive"))
    )
    (net (code "50") (name "Net-(Q6-G)") (class "Default")
      (node (ref "D4") (pin "2") (pinfunction "2_2") (pintype "passive"))
      (node (ref "Q6") (pin "1") (pinfunction "G_1") (pintype "passive"))
      (node (ref "R14") (pin "2") (pinfunction "2_2") (pintype "passive"))
      (node (ref "R17") (pin "1") (pinfunction "1_1") (pintype "passive"))
    )
    (net (code "51") (name "Net-(Q7-G)") (class "Default")
      (node (ref "D5") (pin "2") (pinfunction "2_2") (pintype "passive"))
      (node (ref "Q7") (pin "1") (pinfunction "G_1") (pintype "passive"))
      (node (ref "R15") (pin "2") (pinfunction "2_2") (pintype "passive"))
      (node (ref "R18") (pin "1") (pinfunction "1_1") (pintype "passive"))
    )
    (net (code "52") (name "Net-(Q8-G)") (class "Default")
      (node (ref "Q8") (pin "1") (pinfunction "G_1") (pintype "passive"))
      (node (ref "U4") (pin "2") (pinfunction "~{A}_2") (pintype "output"))
    )
    (net (code "53") (name "Net-(Q9-G)") (class "Default")
      (node (ref "D6") (pin "2") (pinfunction "2_2") (pintype "passive"))
      (node (ref "Q9") (pin "1") (pinfunction "G_1") (pintype "passive"))
      (node (ref "R19") (pin "2") (pinfunction "2_2") (pintype "passive"))
      (node (ref "R22") (pin "1") (pinfunction "1_1") (pintype "passive"))
    )
    (net (code "54") (name "Net-(Q10-D)") (class "Default")
      (node (ref "Q10") (pin "4") (pinfunction "D_4") (pintype "passive"))
      (node (ref "Q9") (pin "4") (pinfunction "D_4") (pintype "passive"))
    )
    (net (code "55") (name "Net-(Q10-G)") (class "Default")
      (node (ref "D7") (pin "2") (pinfunction "2_2") (pintype "passive"))
      (node (ref "Q10") (pin "1") (pinfunction "G_1") (pintype "passive"))
      (node (ref "R20") (pin "2") (pinfunction "2_2") (pintype "passive"))
      (node (ref "R23") (pin "1") (pinfunction "1_1") (pintype "passive"))
    )
    (net (code "56") (name "Net-(R39-Pad1)") (class "Default")
      (node (ref "R39") (pin "1") (pinfunction "1_1") (pintype "passive"))
      (node (ref "U2") (pin "6") (pinfunction "6_6") (pintype "passive"))
      (node (ref "U2") (pin "7") (pinfunction "7_7") (pintype "passive"))
    )
    (net (code "57") (name "Net-(U1-VOUT)") (class "Default")
      (node (ref "R11") (pin "1") (pinfunction "1_1") (pintype "passive"))
      (node (ref "U1") (pin "1") (pinfunction "VOUT_1") (pintype "passive"))
    )
    (net (code "58") (name "Net-(U4B-B)") (class "Default")
      (node (ref "C7") (pin "2") (pinfunction "2_2") (pintype "passive"))
      (node (ref "D12") (pin "2") (pinfunction "2_2") (pintype "passive"))
      (node (ref "D13") (pin "2") (pinfunction "2_2") (pintype "passive"))
      (node (ref "R32") (pin "2") (pinfunction "2_2") (pintype "passive"))
      (node (ref "U4") (pin "3") (pinfunction "B_3") (pintype "input"))
    )
    (net (code "59") (name "Net-(U4B-~{B})") (class "Default")
      (node (ref "D14") (pin "1") (pinfunction "1_1") (pintype "passive"))
      (node (ref "U4") (pin "4") (pinfunction "~{B}_4") (pintype "output"))
      (node (ref "U4") (pin "5") (pinfunction "C_5") (pintype "input"))
    )
    (net (code "60") (name "Net-(U4D-D)") (class "Default")
      (node (ref "C5") (pin "2") (pinfunction "2_2") (pintype "passive"))
      (node (ref "D8") (pin "2") (pinfunction "2_2") (pintype "passive"))
      (node (ref "D9") (pin "2") (pinfunction "2_2") (pintype "passive"))
      (node (ref "R28") (pin "2") (pinfunction "2_2") (pintype "passive"))
      (node (ref "U4") (pin "9") (pinfunction "D_9") (pintype "input"))
    )
    (net (code "61") (name "Net-(U4E-E)") (class "Default")
      (node (ref "C6") (pin "2") (pinfunction "2_2") (pintype "passive"))
      (node (ref "D10") (pin "2") (pinfunction "2_2") (pintype "passive"))
      (node (ref "D11") (pin "2") (pinfunction "2_2") (pintype "passive"))
      (node (ref "R30") (pin "2") (pinfunction "2_2") (pintype "passive"))
      (node (ref "U4") (pin "11") (pinfunction "E_11") (pintype "input"))
    )
    (net (code "62") (name "Net-(U5-2B)") (class "Default")
      (node (ref "U5") (pin "2") (pinfunction "2B_2") (pintype "passive"))
      (node (ref "U5") (pin "3") (pinfunction "3B_3") (pintype "passive"))
      (node (ref "U6") (pin "4") (pinfunction "Y_4") (pintype "output"))
    )
    (net (code "63") (name "unconnected-(U4F-L-Pad12)") (class "Default")
      (node (ref "U4") (pin "12") (pinfunction "L_12") (pintype "output+no_connect"))
    )
    (net (code "64") (name "unconnected-(U5-4B-Pad4)") (class "Default")
      (node (ref "U5") (pin "4") (pinfunction "4B_4") (pintype "passive"))
    )
    (net (code "65") (name "unconnected-(U5-4C-Pad13)") (class "Default")
      (node (ref "U5") (pin "13") (pinfunction "4C_13") (pintype "passive"))
    )
    (net (code "66") (name "unconnected-(U5-5B-Pad5)") (class "Default")
      (node (ref "U5") (pin "5") (pinfunction "5B_5") (pintype "passive"))
    )
    (net (code "67") (name "unconnected-(U5-5C-Pad12)") (class "Default")
      (node (ref "U5") (pin "12") (pinfunction "5C_12") (pintype "passive"))
    )
    (net (code "68") (name "unconnected-(U5-6B-Pad6)") (class "Default")
      (node (ref "U5") (pin "6") (pinfunction "6B_6") (pintype "passive"))
    )
    (net (code "69") (name "unconnected-(U5-6C-Pad11)") (class "Default")
      (node (ref "U5") (pin "11") (pinfunction "6C_11") (pintype "passive"))
    )
    (net (code "70") (name "unconnected-(U5-7B-Pad7)") (class "Default")
      (node (ref "U5") (pin "7") (pinfunction "7B_7") (pintype "passive"))
    )
    (net (code "71") (name "unconnected-(U5-7C-Pad10)") (class "Default")
      (node (ref "U5") (pin "10") (pinfunction "7C_10") (pintype "passive"))
    )
    (net (code "72") (name "unconnected-(U7-7B-Pad7)") (class "Default")
      (node (ref "U7") (pin "7") (pinfunction "7B_7") (pintype "passive"))
    )
    (net (code "73") (name "unconnected-(U7-7C-Pad10)") (class "Default")
      (node (ref "U7") (pin "10") (pinfunction "7C_10") (pintype "passive"))
    )
  )
)
